# Passive_Circuits.net
KiCad netlist of a schematic drawn in Altium Designer
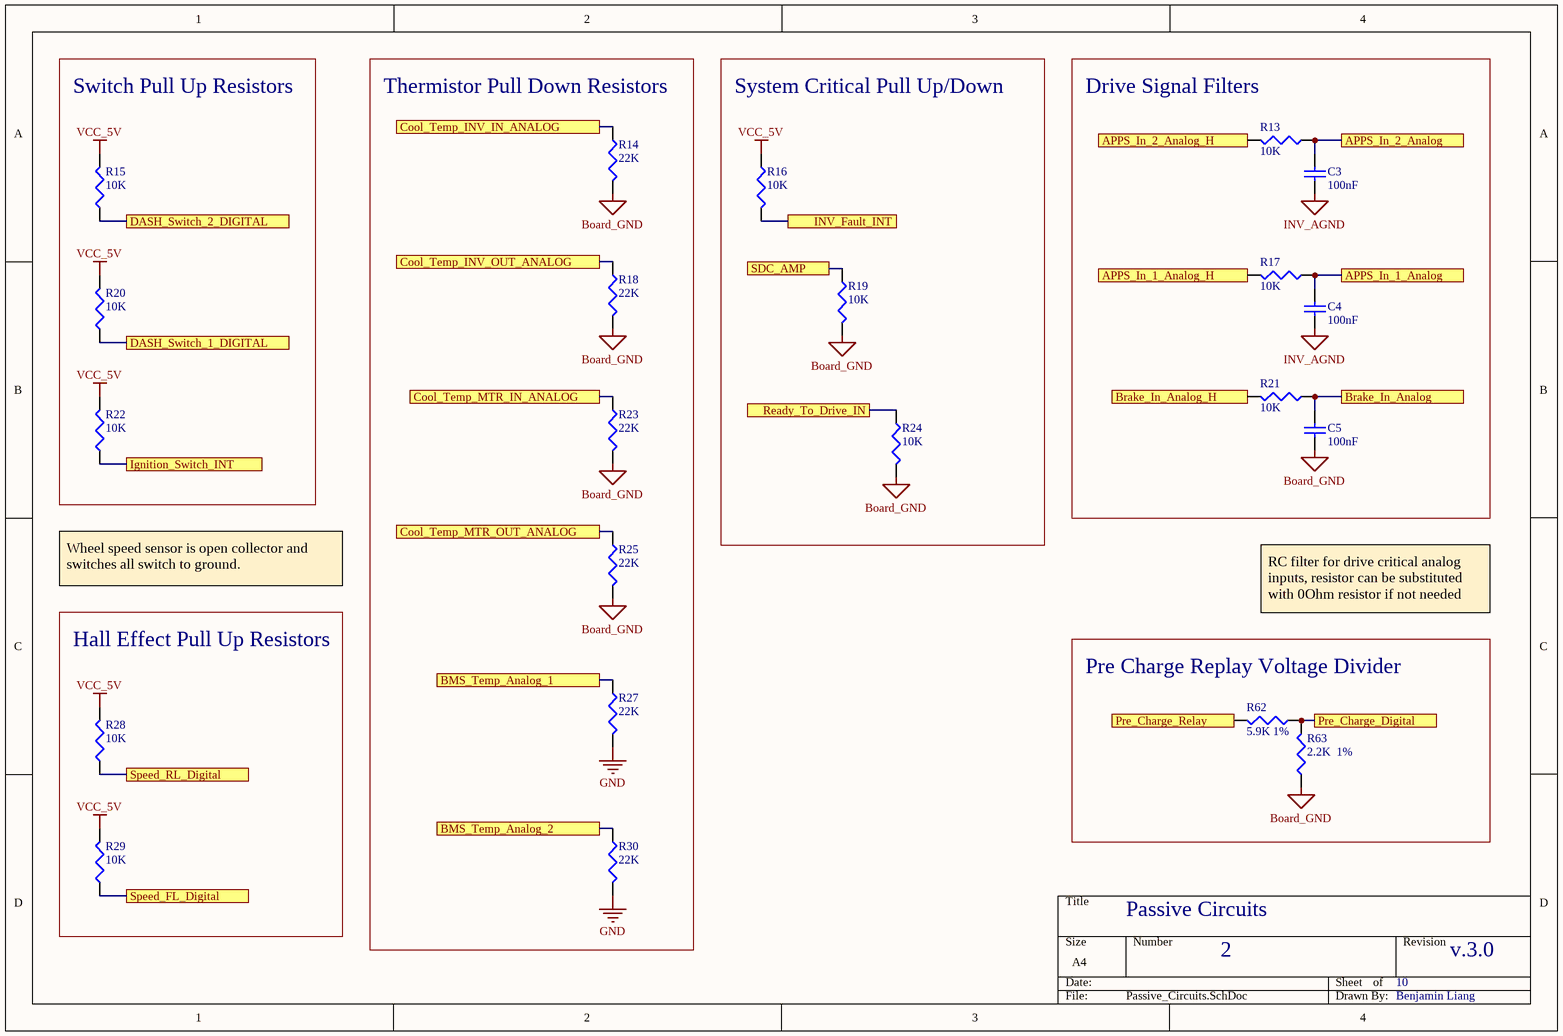
[diagram p0: Passive_Circuits.SchDoc]

(export (version "E")
  (design (tool "Eeschema 10.0.6"))
  (components
    (comp (ref "C3")
      (value "100nF")
      (footprint "C1206")
      (description "Capacitor (Semiconductor SIM Model)")
      (fields (field (name "PUBLISHER") "Altium Limited"))
      (libsource (lib "Miscellaneous Devices") (part "Cap Semi"))
    )
    (comp (ref "C4")
      (value "100nF")
      (footprint "C1206")
      (description "Capacitor (Semiconductor SIM Model)")
      (fields (field (name "PUBLISHER") "Altium Limited"))
      (libsource (lib "Miscellaneous Devices") (part "Cap Semi"))
    )
    (comp (ref "C5")
      (value "100nF")
      (footprint "C1206")
      (description "Capacitor (Semiconductor SIM Model)")
      (fields (field (name "PUBLISHER") "Altium Limited"))
      (libsource (lib "Miscellaneous Devices") (part "Cap Semi"))
    )
    (comp (ref "R13")
      (value "10K")
      (footprint "J1-0603")
      (description "Resistor")
      (fields (field (name "PUBLISHER") "Altium Limited"))
      (libsource (lib "Miscellaneous Devices") (part "Res3"))
    )
    (comp (ref "R14")
      (value "22K")
      (footprint "J1-0603")
      (description "Resistor")
      (fields (field (name "PUBLISHER") "Altium Limited"))
      (libsource (lib "Miscellaneous Devices") (part "Res3"))
    )
    (comp (ref "R15")
      (value "10K")
      (footprint "J1-0603")
      (description "Resistor")
      (fields (field (name "PUBLISHER") "Altium Limited"))
      (libsource (lib "Miscellaneous Devices") (part "Res3"))
    )
    (comp (ref "R16")
      (value "10K")
      (footprint "J1-0603")
      (description "Resistor")
      (fields (field (name "PUBLISHER") "Altium Limited"))
      (libsource (lib "Miscellaneous Devices") (part "Res3"))
    )
    (comp (ref "R17")
      (value "10K")
      (footprint "J1-0603")
      (description "Resistor")
      (fields (field (name "PUBLISHER") "Altium Limited"))
      (libsource (lib "Miscellaneous Devices") (part "Res3"))
    )
    (comp (ref "R18")
      (value "22K")
      (footprint "J1-0603")
      (description "Resistor")
      (fields (field (name "PUBLISHER") "Altium Limited"))
      (libsource (lib "Miscellaneous Devices") (part "Res3"))
    )
    (comp (ref "R19")
      (value "10K")
      (footprint "J1-0603")
      (description "Resistor")
      (fields (field (name "PUBLISHER") "Altium Limited"))
      (libsource (lib "Miscellaneous Devices") (part "Res3"))
    )
    (comp (ref "R20")
      (value "10K")
      (footprint "J1-0603")
      (description "Resistor")
      (fields (field (name "PUBLISHER") "Altium Limited"))
      (libsource (lib "Miscellaneous Devices") (part "Res3"))
    )
    (comp (ref "R21")
      (value "10K")
      (footprint "J1-0603")
      (description "Resistor")
      (fields (field (name "PUBLISHER") "Altium Limited"))
      (libsource (lib "Miscellaneous Devices") (part "Res3"))
    )
    (comp (ref "R22")
      (value "10K")
      (footprint "J1-0603")
      (description "Resistor")
      (fields (field (name "PUBLISHER") "Altium Limited"))
      (libsource (lib "Miscellaneous Devices") (part "Res3"))
    )
    (comp (ref "R23")
      (value "22K")
      (footprint "J1-0603")
      (description "Resistor")
      (fields (field (name "PUBLISHER") "Altium Limited"))
      (libsource (lib "Miscellaneous Devices") (part "Res3"))
    )
    (comp (ref "R24")
      (value "10K")
      (footprint "J1-0603")
      (description "Resistor")
      (fields (field (name "PUBLISHER") "Altium Limited"))
      (libsource (lib "Miscellaneous Devices") (part "Res3"))
    )
    (comp (ref "R25")
      (value "22K")
      (footprint "J1-0603")
      (description "Resistor")
      (fields (field (name "PUBLISHER") "Altium Limited"))
      (libsource (lib "Miscellaneous Devices") (part "Res3"))
    )
    (comp (ref "R27")
      (value "22K")
      (footprint "J1-0603")
      (description "Resistor")
      (fields (field (name "PUBLISHER") "Altium Limited"))
      (libsource (lib "Miscellaneous Devices") (part "Res3"))
    )
    (comp (ref "R28")
      (value "10K")
      (footprint "J1-0603")
      (description "Resistor")
      (fields (field (name "PUBLISHER") "Altium Limited"))
      (libsource (lib "Miscellaneous Devices") (part "Res3"))
    )
    (comp (ref "R29")
      (value "10K")
      (footprint "J1-0603")
      (description "Resistor")
      (fields (field (name "PUBLISHER") "Altium Limited"))
      (libsource (lib "Miscellaneous Devices") (part "Res3"))
    )
    (comp (ref "R30")
      (value "22K")
      (footprint "J1-0603")
      (description "Resistor")
      (fields (field (name "PUBLISHER") "Altium Limited"))
      (libsource (lib "Miscellaneous Devices") (part "Res3"))
    )
    (comp (ref "R62")
      (value "5.9K 1%")
      (footprint "J1-0603")
      (description "Resistor")
      (fields (field (name "PUBLISHER") "Altium Limited"))
      (libsource (lib "Miscellaneous Devices") (part "Res3"))
    )
    (comp (ref "R63")
      (value "2.2K  1%")
      (footprint "J1-0603")
      (description "Resistor")
      (fields (field (name "PUBLISHER") "Altium Limited"))
      (libsource (lib "Miscellaneous Devices") (part "Res3"))
    )
  )
  (nets
    (net (code "1") (name "/APPS_In_1_Analog") (class "Default")
      (node (ref "C4") (pin "1") (pinfunction "1_1") (pintype "passive"))
      (node (ref "R17") (pin "1") (pinfunction "1_1") (pintype "passive"))
    )
    (net (code "2") (name "/APPS_In_1_Analog_H") (class "Default")
      (node (ref "R17") (pin "2") (pinfunction "2_2") (pintype "passive"))
    )
    (net (code "3") (name "/APPS_In_2_Analog") (class "Default")
      (node (ref "C3") (pin "1") (pinfunction "1_1") (pintype "passive"))
      (node (ref "R13") (pin "1") (pinfunction "1_1") (pintype "passive"))
    )
    (net (code "4") (name "/APPS_In_2_Analog_H") (class "Default")
      (node (ref "R13") (pin "2") (pinfunction "2_2") (pintype "passive"))
    )
    (net (code "5") (name "/BMS_Temp_Analog_1") (class "Default")
      (node (ref "R27") (pin "1") (pinfunction "1_1") (pintype "passive"))
    )
    (net (code "6") (name "/BMS_Temp_Analog_2") (class "Default")
      (node (ref "R30") (pin "1") (pinfunction "1_1") (pintype "passive"))
    )
    (net (code "7") (name "/Brake_In_Analog") (class "Default")
      (node (ref "C5") (pin "1") (pinfunction "1_1") (pintype "passive"))
      (node (ref "R21") (pin "1") (pinfunction "1_1") (pintype "passive"))
    )
    (net (code "8") (name "/Brake_In_Analog_H") (class "Default")
      (node (ref "R21") (pin "2") (pinfunction "2_2") (pintype "passive"))
    )
    (net (code "9") (name "/Cool_Temp_INV_IN_ANALOG") (class "Default")
      (node (ref "R14") (pin "1") (pinfunction "1_1") (pintype "passive"))
    )
    (net (code "10") (name "/Cool_Temp_INV_OUT_ANALOG") (class "Default")
      (node (ref "R18") (pin "1") (pinfunction "1_1") (pintype "passive"))
    )
    (net (code "11") (name "/Cool_Temp_MTR_IN_ANALOG") (class "Default")
      (node (ref "R23") (pin "1") (pinfunction "1_1") (pintype "passive"))
    )
    (net (code "12") (name "/Cool_Temp_MTR_OUT_ANALOG") (class "Default")
      (node (ref "R25") (pin "1") (pinfunction "1_1") (pintype "passive"))
    )
    (net (code "13") (name "/DASH_Switch_1_DIGITAL") (class "Default")
      (node (ref "R20") (pin "1") (pinfunction "1_1") (pintype "passive"))
    )
    (net (code "14") (name "/DASH_Switch_2_DIGITAL") (class "Default")
      (node (ref "R15") (pin "1") (pinfunction "1_1") (pintype "passive"))
    )
    (net (code "15") (name "/INV_Fault_INT") (class "Default")
      (node (ref "R16") (pin "2") (pinfunction "2_2") (pintype "passive"))
    )
    (net (code "16") (name "/Ignition_Switch_INT") (class "Default")
      (node (ref "R22") (pin "1") (pinfunction "1_1") (pintype "passive"))
    )
    (net (code "17") (name "/Pre_Charge_Digital") (class "Default")
      (node (ref "R62") (pin "1") (pinfunction "1_1") (pintype "passive"))
      (node (ref "R63") (pin "2") (pinfunction "2_2") (pintype "passive"))
    )
    (net (code "18") (name "/Pre_Charge_Relay") (class "Default")
      (node (ref "R62") (pin "2") (pinfunction "2_2") (pintype "passive"))
    )
    (net (code "19") (name "/Ready_To_Drive_IN") (class "Default")
      (node (ref "R24") (pin "2") (pinfunction "2_2") (pintype "passive"))
    )
    (net (code "20") (name "/SDC_AMP") (class "Default")
      (node (ref "R19") (pin "1") (pinfunction "1_1") (pintype "passive"))
    )
    (net (code "21") (name "/Speed_FL_Digital") (class "Default")
      (node (ref "R29") (pin "1") (pinfunction "1_1") (pintype "passive"))
    )
    (net (code "22") (name "/Speed_RL_Digital") (class "Default")
      (node (ref "R28") (pin "1") (pinfunction "1_1") (pintype "passive"))
    )
    (net (code "23") (name "Board_GND") (class "Default")
      (node (ref "C5") (pin "2") (pinfunction "2_2") (pintype "passive"))
      (node (ref "R14") (pin "2") (pinfunction "2_2") (pintype "passive"))
      (node (ref "R18") (pin "2") (pinfunction "2_2") (pintype "passive"))
      (node (ref "R19") (pin "2") (pinfunction "2_2") (pintype "passive"))
      (node (ref "R23") (pin "2") (pinfunction "2_2") (pintype "passive"))
      (node (ref "R24") (pin "1") (pinfunction "1_1") (pintype "passive"))
      (node (ref "R25") (pin "2") (pinfunction "2_2") (pintype "passive"))
      (node (ref "R63") (pin "1") (pinfunction "1_1") (pintype "passive"))
    )
    (net (code "24") (name "GND") (class "Default")
      (node (ref "R27") (pin "2") (pinfunction "2_2") (pintype "passive"))
      (node (ref "R30") (pin "2") (pinfunction "2_2") (pintype "passive"))
    )
    (net (code "25") (name "INV_AGND") (class "Default")
      (node (ref "C3") (pin "2") (pinfunction "2_2") (pintype "passive"))
      (node (ref "C4") (pin "2") (pinfunction "2_2") (pintype "passive"))
    )
    (net (code "26") (name "VCC_5V") (class "Default")
      (node (ref "R15") (pin "2") (pinfunction "2_2") (pintype "passive"))
      (node (ref "R16") (pin "1") (pinfunction "1_1") (pintype "passive"))
      (node (ref "R20") (pin "2") (pinfunction "2_2") (pintype "passive"))
      (node (ref "R22") (pin "2") (pinfunction "2_2") (pintype "passive"))
      (node (ref "R28") (pin "2") (pinfunction "2_2") (pintype "passive"))
      (node (ref "R29") (pin "2") (pinfunction "2_2") (pintype "passive"))
    )
  )
)
